# Converter_Current_Voltage_Measurement.net
KiCad netlist of a schematic drawn in Altium Designer
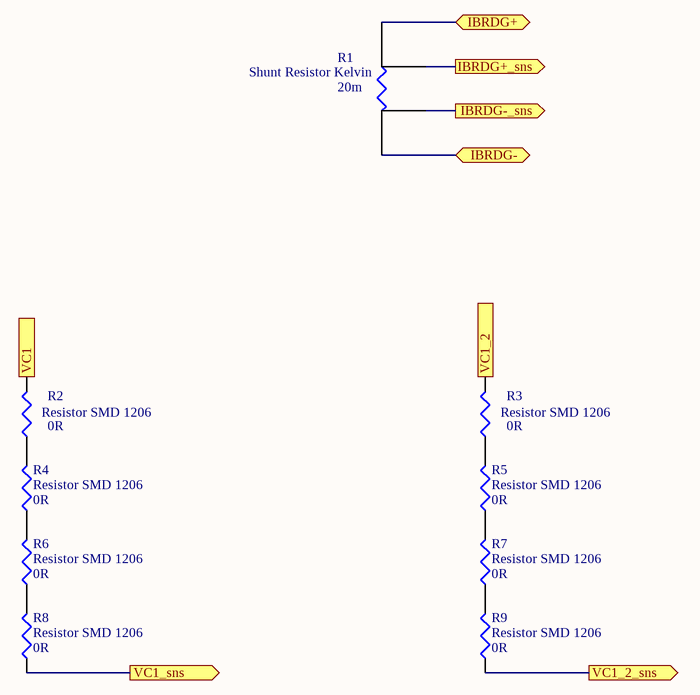
[diagram p0: Converter_Current_Voltage_Measurement.SchDoc]

(export (version "E")
  (design (tool "Eeschema 10.0.6"))
  (components
    (comp (ref "R1")
      (value "Shunt Resistor Kelvin")
      (footprint "Current Sensor:Chip2PinSM127P600-8N")
      (fields (field (name "ALTIUM_VALUE") "20m") (field (name "PUBLISHER") "Altium Limited"))
      (libsource (lib "Current Sensor") (part "Shunt Resistor Kelvin"))
    )
    (comp (ref "R2")
      (value "Resistor SMD 1206")
      (footprint "RESC3116X07N - 1206")
      (fields (field (name "ALTIUM_VALUE") "0R") (field (name "PUBLISHER") "Altium Limited"))
      (libsource (lib "Resistor") (part "Resistor SMD 1206"))
    )
    (comp (ref "R3")
      (value "Resistor SMD 1206")
      (footprint "RESC3116X07N - 1206")
      (fields (field (name "ALTIUM_VALUE") "0R") (field (name "PUBLISHER") "Altium Limited"))
      (libsource (lib "Resistor") (part "Resistor SMD 1206"))
    )
    (comp (ref "R4")
      (value "Resistor SMD 1206")
      (footprint "RESC3116X07N - 1206")
      (fields (field (name "ALTIUM_VALUE") "0R") (field (name "PUBLISHER") "Altium Limited"))
      (libsource (lib "Resistor") (part "Resistor SMD 1206"))
    )
    (comp (ref "R5")
      (value "Resistor SMD 1206")
      (footprint "RESC3116X07N - 1206")
      (fields (field (name "ALTIUM_VALUE") "0R") (field (name "PUBLISHER") "Altium Limited"))
      (libsource (lib "Resistor") (part "Resistor SMD 1206"))
    )
    (comp (ref "R6")
      (value "Resistor SMD 1206")
      (footprint "RESC3116X07N - 1206")
      (fields (field (name "ALTIUM_VALUE") "0R") (field (name "PUBLISHER") "Altium Limited"))
      (libsource (lib "Resistor") (part "Resistor SMD 1206"))
    )
    (comp (ref "R7")
      (value "Resistor SMD 1206")
      (footprint "RESC3116X07N - 1206")
      (fields (field (name "ALTIUM_VALUE") "0R") (field (name "PUBLISHER") "Altium Limited"))
      (libsource (lib "Resistor") (part "Resistor SMD 1206"))
    )
    (comp (ref "R8")
      (value "Resistor SMD 1206")
      (footprint "RESC3116X07N - 1206")
      (fields (field (name "ALTIUM_VALUE") "0R") (field (name "PUBLISHER") "Altium Limited"))
      (libsource (lib "Resistor") (part "Resistor SMD 1206"))
    )
    (comp (ref "R9")
      (value "Resistor SMD 1206")
      (footprint "RESC3116X07N - 1206")
      (fields (field (name "ALTIUM_VALUE") "0R") (field (name "PUBLISHER") "Altium Limited"))
      (libsource (lib "Resistor") (part "Resistor SMD 1206"))
    )
  )
  (nets
    (net (code "1") (name "/IBRDG+") (class "Default")
      (node (ref "R1") (pin "1") (pinfunction "1_1") (pintype "passive"))
    )
    (net (code "2") (name "/IBRDG+_sns") (class "Default")
      (node (ref "R1") (pin "2") (pinfunction "2_2") (pintype "passive"))
    )
    (net (code "3") (name "/IBRDG-") (class "Default")
      (node (ref "R1") (pin "4") (pinfunction "4_4") (pintype "passive"))
    )
    (net (code "4") (name "/IBRDG-_sns") (class "Default")
      (node (ref "R1") (pin "3") (pinfunction "3_3") (pintype "passive"))
    )
    (net (code "5") (name "/VC1") (class "Default")
      (node (ref "R2") (pin "2") (pinfunction "2_2") (pintype "passive"))
    )
    (net (code "6") (name "/VC1_2") (class "Default")
      (node (ref "R3") (pin "2") (pinfunction "2_2") (pintype "passive"))
    )
    (net (code "7") (name "/VC1_2_sns") (class "Default")
      (node (ref "R9") (pin "1") (pinfunction "1_1") (pintype "passive"))
    )
    (net (code "8") (name "/VC1_sns") (class "Default")
      (node (ref "R8") (pin "1") (pinfunction "1_1") (pintype "passive"))
    )
    (net (code "9") (name "Net-(R2-Pad1)") (class "Default")
      (node (ref "R2") (pin "1") (pinfunction "1_1") (pintype "passive"))
      (node (ref "R4") (pin "2") (pinfunction "2_2") (pintype "passive"))
    )
    (net (code "10") (name "Net-(R3-Pad1)") (class "Default")
      (node (ref "R3") (pin "1") (pinfunction "1_1") (pintype "passive"))
      (node (ref "R5") (pin "2") (pinfunction "2_2") (pintype "passive"))
    )
    (net (code "11") (name "Net-(R4-Pad1)") (class "Default")
      (node (ref "R4") (pin "1") (pinfunction "1_1") (pintype "passive"))
      (node (ref "R6") (pin "2") (pinfunction "2_2") (pintype "passive"))
    )
    (net (code "12") (name "Net-(R5-Pad1)") (class "Default")
      (node (ref "R5") (pin "1") (pinfunction "1_1") (pintype "passive"))
      (node (ref "R7") (pin "2") (pinfunction "2_2") (pintype "passive"))
    )
    (net (code "13") (name "Net-(R6-Pad1)") (class "Default")
      (node (ref "R6") (pin "1") (pinfunction "1_1") (pintype "passive"))
      (node (ref "R8") (pin "2") (pinfunction "2_2") (pintype "passive"))
    )
    (net (code "14") (name "Net-(R7-Pad1)") (class "Default")
      (node (ref "R7") (pin "1") (pinfunction "1_1") (pintype "passive"))
      (node (ref "R9") (pin "2") (pinfunction "2_2") (pintype "passive"))
    )
  )
)
